# CPU_IO.net
KiCad netlist of a schematic drawn in Altium Designer
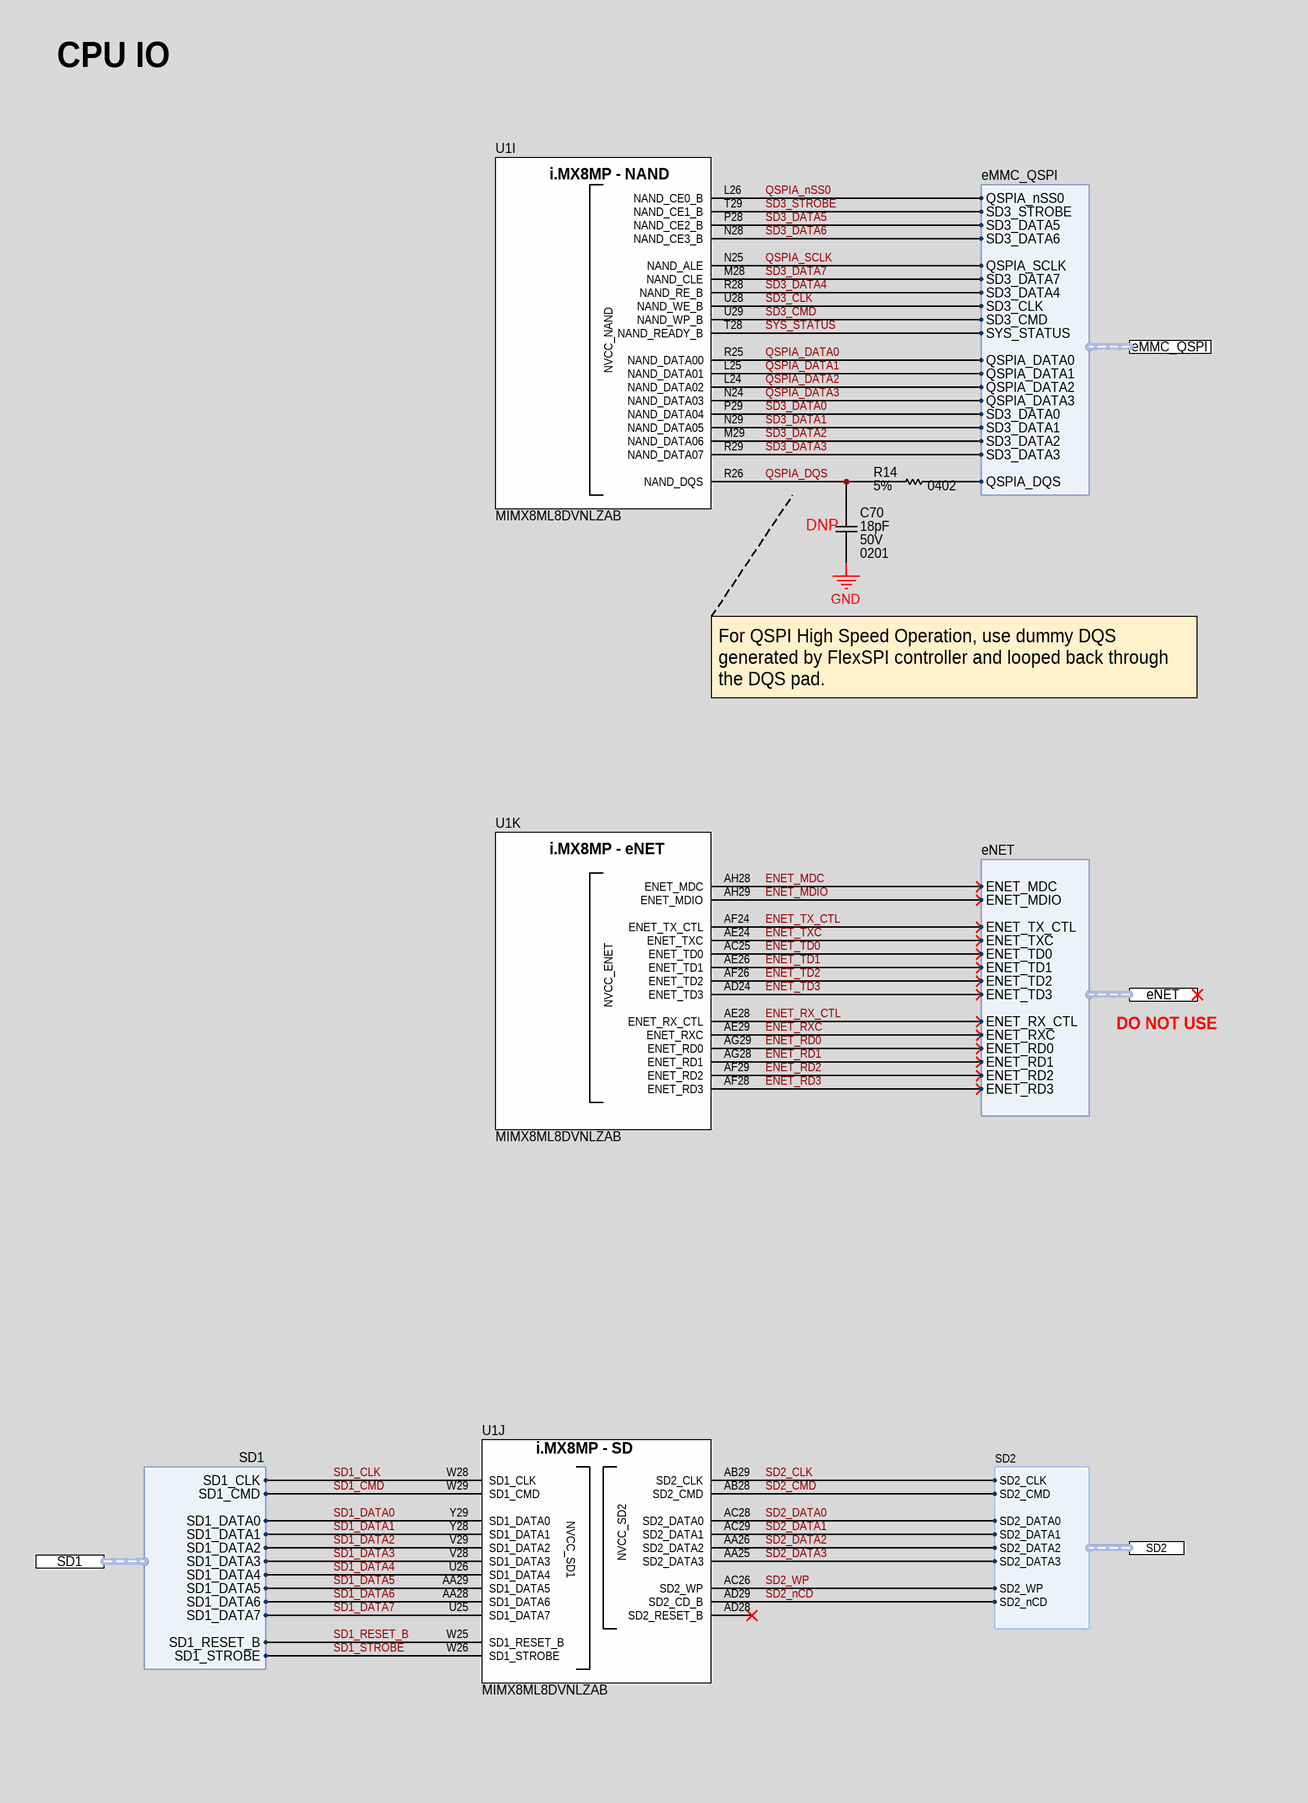
[diagram p0: CPU IO.SchDoc, left]
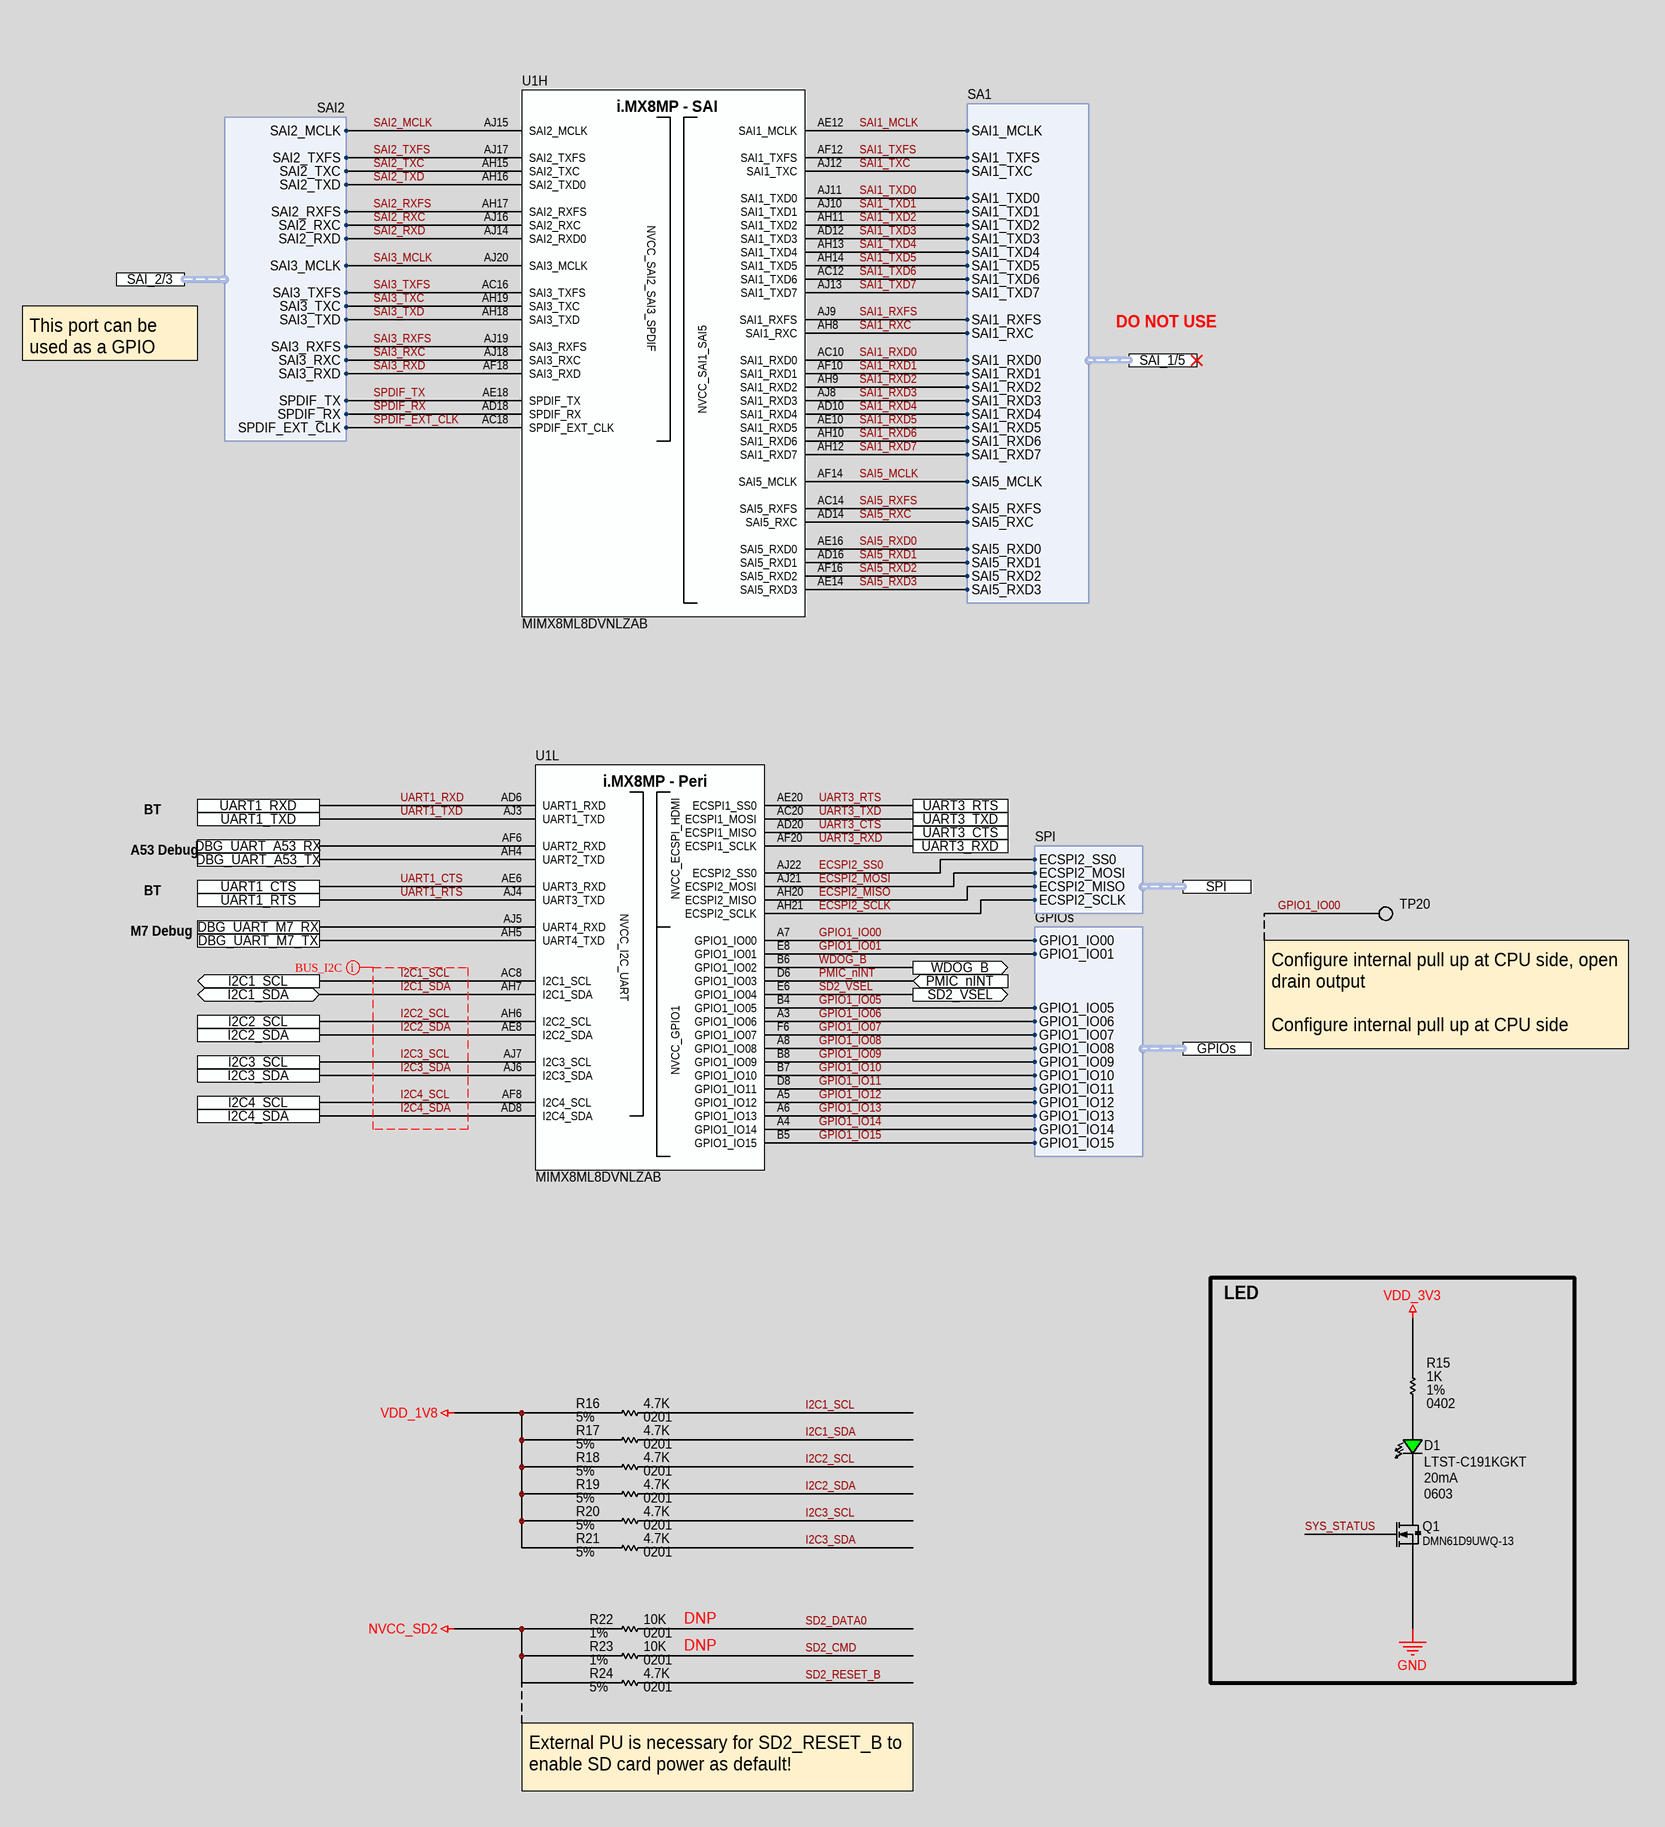
[diagram p1: CPU IO.SchDoc, right]

(export (version "E")
  (design (tool "Eeschema 10.0.6"))
  (components
    (comp (ref "C70")
      (value "GRM0335C1H180JA01D")
      (footprint "CAP_0201_CAPC0603X03N")
      (description "Multilayer Ceramic Capacitor, 18 pF, 50 V, ± 5%, C0G (NP0), 0201 [0603 Metric]")
      (fields
        (field (name "MANUFACTURER") "Murata")
        (field (name "TOLERANCE") "5%")
        (field (name "CAPACITANCE") "18pF")
        (field (name "VOLTAGE RATING") "50V")
        (field (name "CASE/PACKAGE") "0201")
      )
      (libsource (lib "Electronic Devices_LIB") (part "CAP_18PF_50V_NP0_0201"))
    )
    (comp (ref "D1")
      (value "LTST-C191KGKT")
      (footprint "LED_0603-GREEN")
      (description "LTST-C191KGKT Lite-On LED, green, 18-71mcd, 130, 1.9V-2.4V SMD, 0603 1.6x0.8x0.55mm RoHS")
      (fields
        (field (name "MANUFACTURER") "Vishay Lite-On")
        (field (name "TEST CURRENT") "20mA")
        (field (name "CASE/PACKAGE") "0603")
      )
      (libsource (lib "Electronic Devices_LIB") (part "LED_DIO_GREEN_20mA_0603"))
    )
    (comp (ref "Q1")
      (value "DMN61D9UWQ-13")
      (footprint "SOT-323")
      (description "N-Channel Enhancement Mode MOSFET 60V 340mA 3-Pin SOT-323 T/R")
      (fields (field (name "MANUFACTURER") "Diodes"))
      (libsource (lib "Electronic Devices_LIB") (part "TRANS_FET_CHA_N_60V_340mA"))
    )
    (comp (ref "R14")
      (value "ERJ-2GE0R00X")
      (footprint "RES_0402_RESC1005X04N")
      (description "SMD Chip Resistor, Jumper, 0 ohm, 100 mW, 0402 [1005 Metric], Thick Film, General Purpose")
      (fields
        (field (name "MANUFACTURER") "Panasonic")
        (field (name "CASE CODE (IMPERIAL)") "0402")
        (field (name "TOLERANCE") "5%")
      )
      (libsource (lib "Electronic Devices_LIB") (part "RES_0R_5%_100mW_0402"))
    )
    (comp (ref "R15")
      (value "ERJ-2RKF1001X")
      (footprint "RES_0402_RESC1005X04N")
      (description "RES SMD 1K OHM 1% 1/10W 0402")
      (fields
        (field (name "MANUFACTURER") "Panasonic")
        (field (name "RESISTANCE") "1K")
        (field (name "TOLERANCE") "1%")
        (field (name "CASE/PACKAGE") "0402")
      )
      (libsource (lib "Electronic Devices_LIB") (part "RES_1K_1%_100mW_0402"))
    )
    (comp (ref "R16")
      (value "RK73B1HTTC472J")
      (footprint "RES_0201_RESC0603X02N")
      (description "Res Thick Film 0201 4.7K Ohm 5% 0.05W(1/20W) ±200ppm/C Pad SMD Automotive T/R")
      (fields
        (field (name "MANUFACTURER") "KOA Speer")
        (field (name "TOLERANCE") "5%")
        (field (name "RESISTANCE") "4.7K")
        (field (name "CASE/PACKAGE") "0201")
      )
      (libsource (lib "Electronic Devices_LIB") (part "RES_4.7K_5%_50mW_0201"))
    )
    (comp (ref "R17")
      (value "RK73B1HTTC472J")
      (footprint "RES_0201_RESC0603X02N")
      (description "Res Thick Film 0201 4.7K Ohm 5% 0.05W(1/20W) ±200ppm/C Pad SMD Automotive T/R")
      (fields
        (field (name "MANUFACTURER") "KOA Speer")
        (field (name "TOLERANCE") "5%")
        (field (name "RESISTANCE") "4.7K")
        (field (name "CASE/PACKAGE") "0201")
      )
      (libsource (lib "Electronic Devices_LIB") (part "RES_4.7K_5%_50mW_0201"))
    )
    (comp (ref "R18")
      (value "RK73B1HTTC472J")
      (footprint "RES_0201_RESC0603X02N")
      (description "Res Thick Film 0201 4.7K Ohm 5% 0.05W(1/20W) ±200ppm/C Pad SMD Automotive T/R")
      (fields
        (field (name "MANUFACTURER") "KOA Speer")
        (field (name "TOLERANCE") "5%")
        (field (name "RESISTANCE") "4.7K")
        (field (name "CASE/PACKAGE") "0201")
      )
      (libsource (lib "Electronic Devices_LIB") (part "RES_4.7K_5%_50mW_0201"))
    )
    (comp (ref "R19")
      (value "RK73B1HTTC472J")
      (footprint "RES_0201_RESC0603X02N")
      (description "Res Thick Film 0201 4.7K Ohm 5% 0.05W(1/20W) ±200ppm/C Pad SMD Automotive T/R")
      (fields
        (field (name "MANUFACTURER") "KOA Speer")
        (field (name "TOLERANCE") "5%")
        (field (name "RESISTANCE") "4.7K")
        (field (name "CASE/PACKAGE") "0201")
      )
      (libsource (lib "Electronic Devices_LIB") (part "RES_4.7K_5%_50mW_0201"))
    )
    (comp (ref "R20")
      (value "RK73B1HTTC472J")
      (footprint "RES_0201_RESC0603X02N")
      (description "Res Thick Film 0201 4.7K Ohm 5% 0.05W(1/20W) ±200ppm/C Pad SMD Automotive T/R")
      (fields
        (field (name "MANUFACTURER") "KOA Speer")
        (field (name "TOLERANCE") "5%")
        (field (name "RESISTANCE") "4.7K")
        (field (name "CASE/PACKAGE") "0201")
      )
      (libsource (lib "Electronic Devices_LIB") (part "RES_4.7K_5%_50mW_0201"))
    )
    (comp (ref "R21")
      (value "RK73B1HTTC472J")
      (footprint "RES_0201_RESC0603X02N")
      (description "Res Thick Film 0201 4.7K Ohm 5% 0.05W(1/20W) ±200ppm/C Pad SMD Automotive T/R")
      (fields
        (field (name "MANUFACTURER") "KOA Speer")
        (field (name "TOLERANCE") "5%")
        (field (name "RESISTANCE") "4.7K")
        (field (name "CASE/PACKAGE") "0201")
      )
      (libsource (lib "Electronic Devices_LIB") (part "RES_4.7K_5%_50mW_0201"))
    )
    (comp (ref "R22")
      (value "RC0201FR-0710KL")
      (footprint "RES_0201_RESC0603X02N")
      (description "SMD Chip Resistor, 10 kOhm, ± 1%, 50 mW, 0201 [0603 Metric], Thick Film, General Purpose")
      (fields
        (field (name "MANUFACTURER") "Yageo")
        (field (name "TOLERANCE") "1%")
        (field (name "RESISTANCE") "10K")
        (field (name "CASE CODE (IMPERIAL)") "0201")
      )
      (libsource (lib "Electronic Devices_LIB") (part "RES_10K_1/12W_1%_0201"))
    )
    (comp (ref "R23")
      (value "RC0201FR-0710KL")
      (footprint "RES_0201_RESC0603X02N")
      (description "SMD Chip Resistor, 10 kOhm, ± 1%, 50 mW, 0201 [0603 Metric], Thick Film, General Purpose")
      (fields
        (field (name "MANUFACTURER") "Yageo")
        (field (name "TOLERANCE") "1%")
        (field (name "RESISTANCE") "10K")
        (field (name "CASE CODE (IMPERIAL)") "0201")
      )
      (libsource (lib "Electronic Devices_LIB") (part "RES_10K_1/12W_1%_0201"))
    )
    (comp (ref "R24")
      (value "RK73B1HTTC472J")
      (footprint "RES_0201_RESC0603X02N")
      (description "Res Thick Film 0201 4.7K Ohm 5% 0.05W(1/20W) ±200ppm/C Pad SMD Automotive T/R")
      (fields
        (field (name "MANUFACTURER") "KOA Speer")
        (field (name "TOLERANCE") "5%")
        (field (name "RESISTANCE") "4.7K")
        (field (name "CASE/PACKAGE") "0201")
      )
      (libsource (lib "Electronic Devices_LIB") (part "RES_4.7K_5%_50mW_0201"))
    )
    (comp (ref "TP20")
      (value "NO COMPONENT")
      (footprint "TP_PAD_0.5MM_SMD_ROUND")
      (description "Test Point, SMD pad, round, 1.5mm, 1.6mm, 3mm diameter")
      (libsource (lib "Electronic Devices_LIB") (part "TP_PAD_SMD_SMALL"))
    )
    (comp (ref "U1")
      (value "MIMX8ML8DVNLZAB")
      (footprint "IC_MPU_BGA548C50P29X29_1500X1500X148")
      (description "i.MX 8M Plus, Consumer, / TRAY TRAY MULTIPLE DP BAKEABLE RoHS Compliant: Yes")
      (fields (field (name "MANUFACTURER") "NXP Semiconductors"))
      (libsource (lib "Electronic Devices_LIB") (part "IC_MPU_8M_PLUS_MIMX8ML8DVNLZAB"))
    )
  )
  (nets
    (net (code "9") (name "/DBG_UART_A53_RX") (class "Default")
      (node (ref "U1") (pin "AF6") (pinfunction "UART2_RXD_AF6") (pintype "passive"))
    )
    (net (code "10") (name "/DBG_UART_A53_TX") (class "Default")
      (node (ref "U1") (pin "AH4") (pinfunction "UART2_TXD_AH4") (pintype "passive"))
    )
    (net (code "11") (name "/DBG_UART_M7_RX") (class "Default")
      (node (ref "U1") (pin "AJ5") (pinfunction "UART4_RXD_AJ5") (pintype "passive"))
    )
    (net (code "12") (name "/DBG_UART_M7_TX") (class "Default")
      (node (ref "U1") (pin "AH5") (pinfunction "UART4_TXD_AH5") (pintype "passive"))
    )
    (net (code "13") (name "/ECSPI2_MISO") (class "Default")
      (node (ref "U1") (pin "AH20") (pinfunction "ECSPI2_MISO_AH20") (pintype "passive"))
    )
    (net (code "14") (name "/ECSPI2_MOSI") (class "Default")
      (node (ref "U1") (pin "AJ21") (pinfunction "ECSPI2_MOSI_AJ21") (pintype "passive"))
    )
    (net (code "15") (name "/ECSPI2_SCLK") (class "Default")
      (node (ref "U1") (pin "AH21") (pinfunction "ECSPI2_SCLK_AH21") (pintype "passive"))
    )
    (net (code "16") (name "/ECSPI2_SS0") (class "Default")
      (node (ref "U1") (pin "AJ22") (pinfunction "ECSPI2_SS0_AJ22") (pintype "passive"))
    )
    (net (code "17") (name "/ENET_MDC") (class "Default")
      (node (ref "U1") (pin "AH28") (pinfunction "ENET_MDC_AH28") (pintype "passive+no_connect"))
    )
    (net (code "18") (name "/ENET_MDIO") (class "Default")
      (node (ref "U1") (pin "AH29") (pinfunction "ENET_MDIO_AH29") (pintype "passive+no_connect"))
    )
    (net (code "19") (name "/ENET_RD0") (class "Default")
      (node (ref "U1") (pin "AG29") (pinfunction "ENET_RD0_AG29") (pintype "passive+no_connect"))
    )
    (net (code "20") (name "/ENET_RD1") (class "Default")
      (node (ref "U1") (pin "AG28") (pinfunction "ENET_RD1_AG28") (pintype "passive+no_connect"))
    )
    (net (code "21") (name "/ENET_RD2") (class "Default")
      (node (ref "U1") (pin "AF29") (pinfunction "ENET_RD2_AF29") (pintype "passive+no_connect"))
    )
    (net (code "22") (name "/ENET_RD3") (class "Default")
      (node (ref "U1") (pin "AF28") (pinfunction "ENET_RD3_AF28") (pintype "passive+no_connect"))
    )
    (net (code "23") (name "/ENET_RXC") (class "Default")
      (node (ref "U1") (pin "AE29") (pinfunction "ENET_RXC_AE29") (pintype "passive+no_connect"))
    )
    (net (code "24") (name "/ENET_RX_CTL") (class "Default")
      (node (ref "U1") (pin "AE28") (pinfunction "ENET_RX_CTL_AE28") (pintype "passive+no_connect"))
    )
    (net (code "25") (name "/ENET_TD0") (class "Default")
      (node (ref "U1") (pin "AC25") (pinfunction "ENET_TD0_AC25") (pintype "passive+no_connect"))
    )
    (net (code "26") (name "/ENET_TD1") (class "Default")
      (node (ref "U1") (pin "AE26") (pinfunction "ENET_TD1_AE26") (pintype "passive+no_connect"))
    )
    (net (code "27") (name "/ENET_TD2") (class "Default")
      (node (ref "U1") (pin "AF26") (pinfunction "ENET_TD2_AF26") (pintype "passive+no_connect"))
    )
    (net (code "28") (name "/ENET_TD3") (class "Default")
      (node (ref "U1") (pin "AD24") (pinfunction "ENET_TD3_AD24") (pintype "passive+no_connect"))
    )
    (net (code "29") (name "/ENET_TXC") (class "Default")
      (node (ref "U1") (pin "AE24") (pinfunction "ENET_TXC_AE24") (pintype "passive+no_connect"))
    )
    (net (code "30") (name "/ENET_TX_CTL") (class "Default")
      (node (ref "U1") (pin "AF24") (pinfunction "ENET_TX_CTL_AF24") (pintype "passive+no_connect"))
    )
    (net (code "31") (name "/GPIO1_IO00") (class "Default")
      (node (ref "TP20") (pin "1") (pinfunction "1_1") (pintype "passive"))
      (node (ref "U1") (pin "A7") (pinfunction "GPIO1_IO00_A7") (pintype "passive"))
    )
    (net (code "32") (name "/GPIO1_IO01") (class "Default")
      (node (ref "U1") (pin "E8") (pinfunction "GPIO1_IO01_E8") (pintype "passive"))
    )
    (net (code "33") (name "/GPIO1_IO05") (class "Default")
      (node (ref "U1") (pin "B4") (pinfunction "GPIO1_IO05_B4") (pintype "passive"))
    )
    (net (code "34") (name "/GPIO1_IO06") (class "Default")
      (node (ref "U1") (pin "A3") (pinfunction "GPIO1_IO06_A3") (pintype "passive"))
    )
    (net (code "35") (name "/GPIO1_IO07") (class "Default")
      (node (ref "U1") (pin "F6") (pinfunction "GPIO1_IO07_F6") (pintype "passive"))
    )
    (net (code "36") (name "/GPIO1_IO08") (class "Default")
      (node (ref "U1") (pin "A8") (pinfunction "GPIO1_IO08_A8") (pintype "passive"))
    )
    (net (code "37") (name "/GPIO1_IO09") (class "Default")
      (node (ref "U1") (pin "B8") (pinfunction "GPIO1_IO09_B8") (pintype "passive"))
    )
    (net (code "38") (name "/GPIO1_IO10") (class "Default")
      (node (ref "U1") (pin "B7") (pinfunction "GPIO1_IO10_B7") (pintype "passive"))
    )
    (net (code "39") (name "/GPIO1_IO11") (class "Default")
      (node (ref "U1") (pin "D8") (pinfunction "GPIO1_IO11_D8") (pintype "passive"))
    )
    (net (code "40") (name "/GPIO1_IO12") (class "Default")
      (node (ref "U1") (pin "A5") (pinfunction "GPIO1_IO12_A5") (pintype "passive"))
    )
    (net (code "41") (name "/GPIO1_IO13") (class "Default")
      (node (ref "U1") (pin "A6") (pinfunction "GPIO1_IO13_A6") (pintype "passive"))
    )
    (net (code "42") (name "/GPIO1_IO14") (class "Default")
      (node (ref "U1") (pin "A4") (pinfunction "GPIO1_IO14_A4") (pintype "passive"))
    )
    (net (code "43") (name "/GPIO1_IO15") (class "Default")
      (node (ref "U1") (pin "B5") (pinfunction "GPIO1_IO15_B5") (pintype "passive"))
    )
    (net (code "44") (name "/I2C1_SCL") (class "Default")
      (node (ref "R16") (pin "2") (pinfunction "2_2") (pintype "passive"))
      (node (ref "U1") (pin "AC8") (pinfunction "I2C1_SCL_AC8") (pintype "passive"))
    )
    (net (code "45") (name "/I2C1_SDA") (class "Default")
      (node (ref "R17") (pin "2") (pinfunction "2_2") (pintype "passive"))
      (node (ref "U1") (pin "AH7") (pinfunction "I2C1_SDA_AH7") (pintype "passive"))
    )
    (net (code "46") (name "/I2C2_SCL") (class "Default")
      (node (ref "R18") (pin "2") (pinfunction "2_2") (pintype "passive"))
      (node (ref "U1") (pin "AH6") (pinfunction "I2C2_SCL_AH6") (pintype "passive"))
    )
    (net (code "47") (name "/I2C2_SDA") (class "Default")
      (node (ref "R19") (pin "2") (pinfunction "2_2") (pintype "passive"))
      (node (ref "U1") (pin "AE8") (pinfunction "I2C2_SDA_AE8") (pintype "passive"))
    )
    (net (code "48") (name "/I2C3_SCL") (class "Default")
      (node (ref "R20") (pin "2") (pinfunction "2_2") (pintype "passive"))
      (node (ref "U1") (pin "AJ7") (pinfunction "I2C3_SCL_AJ7") (pintype "passive"))
    )
    (net (code "49") (name "/I2C3_SDA") (class "Default")
      (node (ref "R21") (pin "2") (pinfunction "2_2") (pintype "passive"))
      (node (ref "U1") (pin "AJ6") (pinfunction "I2C3_SDA_AJ6") (pintype "passive"))
    )
    (net (code "50") (name "/I2C4_SCL") (class "Default")
      (node (ref "U1") (pin "AF8") (pinfunction "I2C4_SCL_AF8") (pintype "passive"))
    )
    (net (code "51") (name "/I2C4_SDA") (class "Default")
      (node (ref "U1") (pin "AD8") (pinfunction "I2C4_SDA_AD8") (pintype "passive"))
    )
    (net (code "52") (name "/PMIC_nINT") (class "Default")
      (node (ref "U1") (pin "D6") (pinfunction "GPIO1_IO03_D6") (pintype "passive"))
    )
    (net (code "53") (name "/QSPIA_DATA0") (class "Default")
      (node (ref "U1") (pin "R25") (pinfunction "NAND_DATA00_R25") (pintype "passive"))
    )
    (net (code "54") (name "/QSPIA_DATA1") (class "Default")
      (node (ref "U1") (pin "L25") (pinfunction "NAND_DATA01_L25") (pintype "passive"))
    )
    (net (code "55") (name "/QSPIA_DATA2") (class "Default")
      (node (ref "U1") (pin "L24") (pinfunction "NAND_DATA02_L24") (pintype "passive"))
    )
    (net (code "56") (name "/QSPIA_DATA3") (class "Default")
      (node (ref "U1") (pin "N24") (pinfunction "NAND_DATA03_N24") (pintype "passive"))
    )
    (net (code "57") (name "/QSPIA_DQS") (class "Default")
      (node (ref "C70") (pin "2") (pinfunction "2_2") (pintype "passive"))
      (node (ref "R14") (pin "1") (pinfunction "1_1") (pintype "passive"))
      (node (ref "U1") (pin "R26") (pinfunction "NAND_DQS_R26") (pintype "passive"))
    )
    (net (code "58") (name "/QSPIA_SCLK") (class "Default")
      (node (ref "U1") (pin "N25") (pinfunction "NAND_ALE_N25") (pintype "passive"))
    )
    (net (code "59") (name "/QSPIA_nSS0") (class "Default")
      (node (ref "U1") (pin "L26") (pinfunction "NAND_CE0_B_L26") (pintype "passive"))
    )
    (net (code "60") (name "/SAI1_MCLK") (class "Default")
      (node (ref "U1") (pin "AE12") (pinfunction "SAI1_MCLK_AE12") (pintype "passive"))
    )
    (net (code "61") (name "/SAI1_RXC") (class "Default")
      (node (ref "U1") (pin "AH8") (pinfunction "SAI1_RXC_AH8") (pintype "passive"))
    )
    (net (code "62") (name "/SAI1_RXD0") (class "Default")
      (node (ref "U1") (pin "AC10") (pinfunction "SAI1_RXD0_AC10") (pintype "passive"))
    )
    (net (code "63") (name "/SAI1_RXD1") (class "Default")
      (node (ref "U1") (pin "AF10") (pinfunction "SAI1_RXD1_AF10") (pintype "passive"))
    )
    (net (code "64") (name "/SAI1_RXD2") (class "Default")
      (node (ref "U1") (pin "AH9") (pinfunction "SAI1_RXD2_AH9") (pintype "passive"))
    )
    (net (code "65") (name "/SAI1_RXD3") (class "Default")
      (node (ref "U1") (pin "AJ8") (pinfunction "SAI1_RXD3_AJ8") (pintype "passive"))
    )
    (net (code "66") (name "/SAI1_RXD4") (class "Default")
      (node (ref "U1") (pin "AD10") (pinfunction "SAI1_RXD4_AD10") (pintype "passive"))
    )
    (net (code "67") (name "/SAI1_RXD5") (class "Default")
      (node (ref "U1") (pin "AE10") (pinfunction "SAI1_RXD5_AE10") (pintype "passive"))
    )
    (net (code "68") (name "/SAI1_RXD6") (class "Default")
      (node (ref "U1") (pin "AH10") (pinfunction "SAI1_RXD6_AH10") (pintype "passive"))
    )
    (net (code "69") (name "/SAI1_RXD7") (class "Default")
      (node (ref "U1") (pin "AH12") (pinfunction "SAI1_RXD7_AH12") (pintype "passive"))
    )
    (net (code "70") (name "/SAI1_RXFS") (class "Default")
      (node (ref "U1") (pin "AJ9") (pinfunction "SAI1_RXFS_AJ9") (pintype "passive"))
    )
    (net (code "71") (name "/SAI1_TXC") (class "Default")
      (node (ref "U1") (pin "AJ12") (pinfunction "SAI1_TXC_AJ12") (pintype "passive"))
    )
    (net (code "72") (name "/SAI1_TXD0") (class "Default")
      (node (ref "U1") (pin "AJ11") (pinfunction "SAI1_TXD0_AJ11") (pintype "passive"))
    )
    (net (code "73") (name "/SAI1_TXD1") (class "Default")
      (node (ref "U1") (pin "AJ10") (pinfunction "SAI1_TXD1_AJ10") (pintype "passive"))
    )
    (net (code "74") (name "/SAI1_TXD2") (class "Default")
      (node (ref "U1") (pin "AH11") (pinfunction "SAI1_TXD2_AH11") (pintype "passive"))
    )
    (net (code "75") (name "/SAI1_TXD3") (class "Default")
      (node (ref "U1") (pin "AD12") (pinfunction "SAI1_TXD3_AD12") (pintype "passive"))
    )
    (net (code "76") (name "/SAI1_TXD4") (class "Default")
      (node (ref "U1") (pin "AH13") (pinfunction "SAI1_TXD4_AH13") (pintype "passive"))
    )
    (net (code "77") (name "/SAI1_TXD5") (class "Default")
      (node (ref "U1") (pin "AH14") (pinfunction "SAI1_TXD5_AH14") (pintype "passive"))
    )
    (net (code "78") (name "/SAI1_TXD6") (class "Default")
      (node (ref "U1") (pin "AC12") (pinfunction "SAI1_TXD6_AC12") (pintype "passive"))
    )
    (net (code "79") (name "/SAI1_TXD7") (class "Default")
      (node (ref "U1") (pin "AJ13") (pinfunction "SAI1_TXD7_AJ13") (pintype "passive"))
    )
    (net (code "80") (name "/SAI1_TXFS") (class "Default")
      (node (ref "U1") (pin "AF12") (pinfunction "SAI1_TXFS_AF12") (pintype "passive"))
    )
    (net (code "81") (name "/SAI2_MCLK") (class "Default")
      (node (ref "U1") (pin "AJ15") (pinfunction "SAI2_MCLK_AJ15") (pintype "passive"))
    )
    (net (code "82") (name "/SAI2_RXC") (class "Default")
      (node (ref "U1") (pin "AJ16") (pinfunction "SAI2_RXC_AJ16") (pintype "passive"))
    )
    (net (code "83") (name "/SAI2_RXD") (class "Default")
      (node (ref "U1") (pin "AJ14") (pinfunction "SAI2_RXD0_AJ14") (pintype "passive"))
    )
    (net (code "84") (name "/SAI2_RXFS") (class "Default")
      (node (ref "U1") (pin "AH17") (pinfunction "SAI2_RXFS_AH17") (pintype "passive"))
    )
    (net (code "85") (name "/SAI2_TXC") (class "Default")
      (node (ref "U1") (pin "AH15") (pinfunction "SAI2_TXC_AH15") (pintype "passive"))
    )
    (net (code "86") (name "/SAI2_TXD") (class "Default")
      (node (ref "U1") (pin "AH16") (pinfunction "SAI2_TXD0_AH16") (pintype "passive"))
    )
    (net (code "87") (name "/SAI2_TXFS") (class "Default")
      (node (ref "U1") (pin "AJ17") (pinfunction "SAI2_TXFS_AJ17") (pintype "passive"))
    )
    (net (code "88") (name "/SAI3_MCLK") (class "Default")
      (node (ref "U1") (pin "AJ20") (pinfunction "SAI3_MCLK_AJ20") (pintype "passive"))
    )
    (net (code "89") (name "/SAI3_RXC") (class "Default")
      (node (ref "U1") (pin "AJ18") (pinfunction "SAI3_RXC_AJ18") (pintype "passive"))
    )
    (net (code "90") (name "/SAI3_RXD") (class "Default")
      (node (ref "U1") (pin "AF18") (pinfunction "SAI3_RXD_AF18") (pintype "passive"))
    )
    (net (code "91") (name "/SAI3_RXFS") (class "Default")
      (node (ref "U1") (pin "AJ19") (pinfunction "SAI3_RXFS_AJ19") (pintype "passive"))
    )
    (net (code "92") (name "/SAI3_TXC") (class "Default")
      (node (ref "U1") (pin "AH19") (pinfunction "SAI3_TXC_AH19") (pintype "passive"))
    )
    (net (code "93") (name "/SAI3_TXD") (class "Default")
      (node (ref "U1") (pin "AH18") (pinfunction "SAI3_TXD_AH18") (pintype "passive"))
    )
    (net (code "94") (name "/SAI3_TXFS") (class "Default")
      (node (ref "U1") (pin "AC16") (pinfunction "SAI3_TXFS_AC16") (pintype "passive"))
    )
    (net (code "95") (name "/SAI5_MCLK") (class "Default")
      (node (ref "U1") (pin "AF14") (pinfunction "SAI5_MCLK_AF14") (pintype "passive"))
    )
    (net (code "96") (name "/SAI5_RXC") (class "Default")
      (node (ref "U1") (pin "AD14") (pinfunction "SAI5_RXC_AD14") (pintype "passive"))
    )
    (net (code "97") (name "/SAI5_RXD0") (class "Default")
      (node (ref "U1") (pin "AE16") (pinfunction "SAI5_RXD0_AE16") (pintype "passive"))
    )
    (net (code "98") (name "/SAI5_RXD1") (class "Default")
      (node (ref "U1") (pin "AD16") (pinfunction "SAI5_RXD1_AD16") (pintype "passive"))
    )
    (net (code "99") (name "/SAI5_RXD2") (class "Default")
      (node (ref "U1") (pin "AF16") (pinfunction "SAI5_RXD2_AF16") (pintype "passive"))
    )
    (net (code "100") (name "/SAI5_RXD3") (class "Default")
      (node (ref "U1") (pin "AE14") (pinfunction "SAI5_RXD3_AE14") (pintype "passive"))
    )
    (net (code "101") (name "/SAI5_RXFS") (class "Default")
      (node (ref "U1") (pin "AC14") (pinfunction "SAI5_RXFS_AC14") (pintype "passive"))
    )
    (net (code "102") (name "/SD1_CLK") (class "Default")
      (node (ref "U1") (pin "W28") (pinfunction "SD1_CLK_W28") (pintype "passive"))
    )
    (net (code "103") (name "/SD1_CMD") (class "Default")
      (node (ref "U1") (pin "W29") (pinfunction "SD1_CMD_W29") (pintype "passive"))
    )
    (net (code "104") (name "/SD1_DATA0") (class "Default")
      (node (ref "U1") (pin "Y29") (pinfunction "SD1_DATA0_Y29") (pintype "passive"))
    )
    (net (code "105") (name "/SD1_DATA1") (class "Default")
      (node (ref "U1") (pin "Y28") (pinfunction "SD1_DATA1_Y28") (pintype "passive"))
    )
    (net (code "106") (name "/SD1_DATA2") (class "Default")
      (node (ref "U1") (pin "V29") (pinfunction "SD1_DATA2_V29") (pintype "passive"))
    )
    (net (code "107") (name "/SD1_DATA3") (class "Default")
      (node (ref "U1") (pin "V28") (pinfunction "SD1_DATA3_V28") (pintype "passive"))
    )
    (net (code "108") (name "/SD1_DATA4") (class "Default")
      (node (ref "U1") (pin "U26") (pinfunction "SD1_DATA4_U26") (pintype "passive"))
    )
    (net (code "109") (name "/SD1_DATA5") (class "Default")
      (node (ref "U1") (pin "AA29") (pinfunction "SD1_DATA5_AA29") (pintype "passive"))
    )
    (net (code "110") (name "/SD1_DATA6") (class "Default")
      (node (ref "U1") (pin "AA28") (pinfunction "SD1_DATA6_AA28") (pintype "passive"))
    )
    (net (code "111") (name "/SD1_DATA7") (class "Default")
      (node (ref "U1") (pin "U25") (pinfunction "SD1_DATA7_U25") (pintype "passive"))
    )
    (net (code "112") (name "/SD1_RESET_B") (class "Default")
      (node (ref "U1") (pin "W25") (pinfunction "SD1_RESET_B_W25") (pintype "passive"))
    )
    (net (code "113") (name "/SD1_STROBE") (class "Default")
      (node (ref "U1") (pin "W26") (pinfunction "SD1_STROBE_W26") (pintype "passive"))
    )
    (net (code "114") (name "/SD2_CLK") (class "Default")
      (node (ref "U1") (pin "AB29") (pinfunction "SD2_CLK_AB29") (pintype "passive"))
    )
    (net (code "115") (name "/SD2_CMD") (class "Default")
      (node (ref "R23") (pin "2") (pinfunction "2_2") (pintype "passive"))
      (node (ref "U1") (pin "AB28") (pinfunction "SD2_CMD_AB28") (pintype "passive"))
    )
    (net (code "116") (name "/SD2_DATA0") (class "Default")
      (node (ref "R22") (pin "2") (pinfunction "2_2") (pintype "passive"))
      (node (ref "U1") (pin "AC28") (pinfunction "SD2_DATA0_AC28") (pintype "passive"))
    )
    (net (code "117") (name "/SD2_DATA1") (class "Default")
      (node (ref "U1") (pin "AC29") (pinfunction "SD2_DATA1_AC29") (pintype "passive"))
    )
    (net (code "118") (name "/SD2_DATA2") (class "Default")
      (node (ref "U1") (pin "AA26") (pinfunction "SD2_DATA2_AA26") (pintype "passive"))
    )
    (net (code "119") (name "/SD2_DATA3") (class "Default")
      (node (ref "U1") (pin "AA25") (pinfunction "SD2_DATA3_AA25") (pintype "passive"))
    )
    (net (code "120") (name "/SD2_RESET_B") (class "Default")
      (node (ref "R24") (pin "2") (pinfunction "2_2") (pintype "passive"))
    )
    (net (code "121") (name "/SD2_VSEL") (class "Default")
      (node (ref "U1") (pin "E6") (pinfunction "GPIO1_IO04_E6") (pintype "passive"))
    )
    (net (code "122") (name "/SD2_WP") (class "Default")
      (node (ref "U1") (pin "AC26") (pinfunction "SD2_WP_AC26") (pintype "passive"))
    )
    (net (code "123") (name "/SD2_nCD") (class "Default")
      (node (ref "U1") (pin "AD29") (pinfunction "SD2_CD_B_AD29") (pintype "passive"))
    )
    (net (code "124") (name "/SD3_CLK") (class "Default")
      (node (ref "U1") (pin "U28") (pinfunction "NAND_WE_B_U28") (pintype "passive"))
    )
    (net (code "125") (name "/SD3_CMD") (class "Default")
      (node (ref "U1") (pin "U29") (pinfunction "NAND_WP_B_U29") (pintype "passive"))
    )
    (net (code "126") (name "/SD3_DATA0") (class "Default")
      (node (ref "U1") (pin "P29") (pinfunction "NAND_DATA04_P29") (pintype "passive"))
    )
    (net (code "127") (name "/SD3_DATA1") (class "Default")
      (node (ref "U1") (pin "N29") (pinfunction "NAND_DATA05_N29") (pintype "passive"))
    )
    (net (code "128") (name "/SD3_DATA2") (class "Default")
      (node (ref "U1") (pin "M29") (pinfunction "NAND_DATA06_M29") (pintype "passive"))
    )
    (net (code "129") (name "/SD3_DATA3") (class "Default")
      (node (ref "U1") (pin "R29") (pinfunction "NAND_DATA07_R29") (pintype "passive"))
    )
    (net (code "130") (name "/SD3_DATA4") (class "Default")
      (node (ref "U1") (pin "R28") (pinfunction "NAND_RE_B_R28") (pintype "passive"))
    )
    (net (code "131") (name "/SD3_DATA5") (class "Default")
      (node (ref "U1") (pin "P28") (pinfunction "NAND_CE2_B_P28") (pintype "passive"))
    )
    (net (code "132") (name "/SD3_DATA6") (class "Default")
      (node (ref "U1") (pin "N28") (pinfunction "NAND_CE3_B_N28") (pintype "passive"))
    )
    (net (code "133") (name "/SD3_DATA7") (class "Default")
      (node (ref "U1") (pin "M28") (pinfunction "NAND_CLE_M28") (pintype "passive"))
    )
    (net (code "134") (name "/SD3_STROBE") (class "Default")
      (node (ref "U1") (pin "T29") (pinfunction "NAND_CE1_B_T29") (pintype "passive"))
    )
    (net (code "135") (name "/SPDIF_EXT_CLK") (class "Default")
      (node (ref "U1") (pin "AC18") (pinfunction "SPDIF_EXT_CLK_AC18") (pintype "passive"))
    )
    (net (code "136") (name "/SPDIF_RX") (class "Default")
      (node (ref "U1") (pin "AD18") (pinfunction "SPDIF_RX_AD18") (pintype "passive"))
    )
    (net (code "137") (name "/SPDIF_TX") (class "Default")
      (node (ref "U1") (pin "AE18") (pinfunction "SPDIF_TX_AE18") (pintype "passive"))
    )
    (net (code "138") (name "/SYS_STATUS") (class "Default")
      (node (ref "Q1") (pin "G") (pinfunction "G_G") (pintype "passive"))
      (node (ref "U1") (pin "T28") (pinfunction "NAND_READY_B_T28") (pintype "passive"))
    )
    (net (code "139") (name "/UART1_CTS") (class "Default")
      (node (ref "U1") (pin "AE6") (pinfunction "UART3_RXD_AE6") (pintype "passive"))
    )
    (net (code "140") (name "/UART1_RTS") (class "Default")
      (node (ref "U1") (pin "AJ4") (pinfunction "UART3_TXD_AJ4") (pintype "passive"))
    )
    (net (code "141") (name "/UART1_RXD") (class "Default")
      (node (ref "U1") (pin "AD6") (pinfunction "UART1_RXD_AD6") (pintype "passive"))
    )
    (net (code "142") (name "/UART1_TXD") (class "Default")
      (node (ref "U1") (pin "AJ3") (pinfunction "UART1_TXD_AJ3") (pintype "passive"))
    )
    (net (code "143") (name "/UART3_CTS") (class "Default")
      (node (ref "U1") (pin "AD20") (pinfunction "ECSPI1_MISO_AD20") (pintype "passive"))
    )
    (net (code "144") (name "/UART3_RTS") (class "Default")
      (node (ref "U1") (pin "AE20") (pinfunction "ECSPI1_SS0_AE20") (pintype "passive"))
    )
    (net (code "145") (name "/UART3_RXD") (class "Default")
      (node (ref "U1") (pin "AF20") (pinfunction "ECSPI1_SCLK_AF20") (pintype "passive"))
    )
    (net (code "146") (name "/UART3_TXD") (class "Default")
      (node (ref "U1") (pin "AC20") (pinfunction "ECSPI1_MOSI_AC20") (pintype "passive"))
    )
    (net (code "147") (name "/WDOG_B") (class "Default")
      (node (ref "U1") (pin "B6") (pinfunction "GPIO1_IO02_B6") (pintype "passive"))
    )
    (net (code "156") (name "GND") (class "Default")
      (node (ref "C70") (pin "1") (pinfunction "1_1") (pintype "passive"))
      (node (ref "Q1") (pin "S") (pinfunction "S_S") (pintype "passive"))
    )
    (net (code "157") (name "NVCC_SD2") (class "Default")
      (node (ref "R22") (pin "1") (pinfunction "1_1") (pintype "passive"))
      (node (ref "R23") (pin "1") (pinfunction "1_1") (pintype "passive"))
      (node (ref "R24") (pin "1") (pinfunction "1_1") (pintype "passive"))
    )
    (net (code "158") (name "Net-(D1-A)") (class "Default")
      (node (ref "D1") (pin "2") (pinfunction "A_2") (pintype "passive"))
      (node (ref "R15") (pin "1") (pinfunction "1_1") (pintype "passive"))
    )
    (net (code "159") (name "Net-(D1-C)") (class "Default")
      (node (ref "D1") (pin "1") (pinfunction "C_1") (pintype "passive"))
      (node (ref "Q1") (pin "D") (pinfunction "D_D") (pintype "passive"))
    )
    (net (code "160") (name "VDD_1V8") (class "Default")
      (node (ref "R16") (pin "1") (pinfunction "1_1") (pintype "passive"))
      (node (ref "R17") (pin "1") (pinfunction "1_1") (pintype "passive"))
      (node (ref "R18") (pin "1") (pinfunction "1_1") (pintype "passive"))
      (node (ref "R19") (pin "1") (pinfunction "1_1") (pintype "passive"))
      (node (ref "R20") (pin "1") (pinfunction "1_1") (pintype "passive"))
      (node (ref "R21") (pin "1") (pinfunction "1_1") (pintype "passive"))
    )
    (net (code "161") (name "VDD_3V3") (class "Default")
      (node (ref "R15") (pin "2") (pinfunction "2_2") (pintype "passive"))
    )
    (net (code "162") (name "unconnected-(R14-Pad2)") (class "Default")
      (node (ref "R14") (pin "2") (pinfunction "2_2") (pintype "passive"))
    )
    (net (code "163") (name "unconnected-(U1J-SD2_RESET_B-PadAD28)") (class "Default")
      (node (ref "U1") (pin "AD28") (pinfunction "SD2_RESET_B_AD28") (pintype "passive+no_connect"))
    )
  )
)
